# horus_psu.net
KiCad netlist of a schematic drawn in Altium Designer
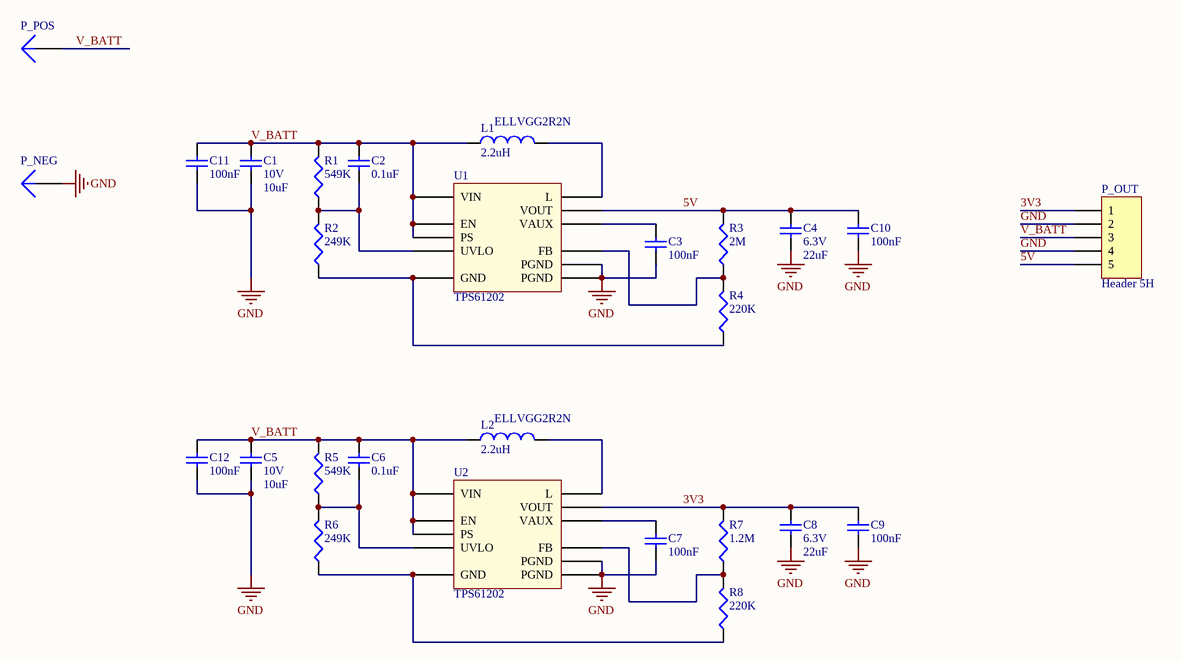
[diagram p0: horus_psu.SchDoc]

(export (version "E")
  (design (tool "Eeschema 10.0.6"))
  (components
    (comp (ref "C1")
      (value "10V")
      (footprint "C1206")
      (description "Capacitor (Semiconductor SIM Model)")
      (fields (field (name "ALTIUM_VALUE") "10uF") (field (name "PUBLISHER") "Altium Limited"))
      (libsource (lib "Miscellaneous Devices") (part "Cap Semi"))
    )
    (comp (ref "C2")
      (value "0.1uF")
      (footprint "1608[0603]")
      (description "Capacitor (Semiconductor SIM Model)")
      (fields (field (name "Comment") "Cap Semi") (field (name "PUBLISHER") "Altium Limited"))
      (libsource (lib "Miscellaneous Devices") (part "Cap Semi"))
    )
    (comp (ref "C3")
      (value "100nF")
      (footprint "1608[0603]")
      (description "Capacitor (Semiconductor SIM Model)")
      (fields (field (name "Comment") "Cap Semi") (field (name "PUBLISHER") "Altium Limited"))
      (libsource (lib "Miscellaneous Devices") (part "Cap Semi"))
    )
    (comp (ref "C4")
      (value "6.3V")
      (footprint "6-0805_N")
      (description "Capacitor (Semiconductor SIM Model)")
      (fields (field (name "ALTIUM_VALUE") "22uF") (field (name "PUBLISHER") "Altium Limited"))
      (libsource (lib "Miscellaneous Devices") (part "Cap Semi"))
    )
    (comp (ref "C5")
      (value "10V")
      (footprint "C1206")
      (description "Capacitor (Semiconductor SIM Model)")
      (fields (field (name "ALTIUM_VALUE") "10uF") (field (name "PUBLISHER") "Altium Limited"))
      (libsource (lib "Miscellaneous Devices") (part "Cap Semi"))
    )
    (comp (ref "C6")
      (value "0.1uF")
      (footprint "1608[0603]")
      (description "Capacitor (Semiconductor SIM Model)")
      (fields (field (name "Comment") "Cap Semi") (field (name "PUBLISHER") "Altium Limited"))
      (libsource (lib "Miscellaneous Devices") (part "Cap Semi"))
    )
    (comp (ref "C7")
      (value "100nF")
      (footprint "1608[0603]")
      (description "Capacitor (Semiconductor SIM Model)")
      (fields (field (name "Comment") "Cap Semi") (field (name "PUBLISHER") "Altium Limited"))
      (libsource (lib "Miscellaneous Devices") (part "Cap Semi"))
    )
    (comp (ref "C8")
      (value "6.3V")
      (footprint "6-0805_N")
      (description "Capacitor (Semiconductor SIM Model)")
      (fields (field (name "ALTIUM_VALUE") "22uF") (field (name "PUBLISHER") "Altium Limited"))
      (libsource (lib "Miscellaneous Devices") (part "Cap Semi"))
    )
    (comp (ref "C9")
      (value "100nF")
      (footprint "1608[0603]")
      (description "Capacitor (Semiconductor SIM Model)")
      (fields (field (name "Comment") "Cap Semi") (field (name "PUBLISHER") "Altium Limited"))
      (libsource (lib "Miscellaneous Devices") (part "Cap Semi"))
    )
    (comp (ref "C10")
      (value "100nF")
      (footprint "1608[0603]")
      (description "Capacitor (Semiconductor SIM Model)")
      (fields (field (name "Comment") "Cap Semi") (field (name "PUBLISHER") "Altium Limited"))
      (libsource (lib "Miscellaneous Devices") (part "Cap Semi"))
    )
    (comp (ref "C11")
      (value "100nF")
      (footprint "1608[0603]")
      (description "Capacitor (Semiconductor SIM Model)")
      (fields (field (name "Comment") "Cap Semi") (field (name "PUBLISHER") "Altium Limited"))
      (libsource (lib "Miscellaneous Devices") (part "Cap Semi"))
    )
    (comp (ref "C12")
      (value "100nF")
      (footprint "1608[0603]")
      (description "Capacitor (Semiconductor SIM Model)")
      (fields (field (name "Comment") "Cap Semi") (field (name "PUBLISHER") "Altium Limited"))
      (libsource (lib "Miscellaneous Devices") (part "Cap Semi"))
    )
    (comp (ref "L1")
      (value "ELLVGG2R2N")
      (footprint "ELLVGG")
      (description "Inductor")
      (fields (field (name "ALTIUM_VALUE") "2.2uH") (field (name "PUBLISHER") "Altium Limited"))
      (libsource (lib "Miscellaneous Devices") (part "Inductor"))
    )
    (comp (ref "L2")
      (value "ELLVGG2R2N")
      (footprint "ELLVGG")
      (description "Inductor")
      (fields (field (name "ALTIUM_VALUE") "2.2uH") (field (name "PUBLISHER") "Altium Limited"))
      (libsource (lib "Miscellaneous Devices") (part "Inductor"))
    )
    (comp (ref "P_NEG")
      (value "Plug")
      (footprint "PIN1")
      (fields (field (name "PUBLISHER") "Altium Limited"))
      (libsource (lib "Miscellaneous Connectors") (part "Plug"))
    )
    (comp (ref "P_OUT")
      (value "Header 5H")
      (footprint "HDR1X5H")
      (description "Header, 5-Pin, Right Angle")
      (fields (field (name "PUBLISHER") "Altium Limited"))
      (libsource (lib "Miscellaneous Connectors") (part "Header 5H"))
    )
    (comp (ref "P_POS")
      (value "Plug")
      (footprint "PIN1")
      (fields (field (name "PUBLISHER") "Altium Limited"))
      (libsource (lib "Miscellaneous Connectors") (part "Plug"))
    )
    (comp (ref "R1")
      (value "549K")
      (footprint "J1-0603")
      (description "Resistor")
      (fields (field (name "Comment") "Res3") (field (name "PUBLISHER") "Altium Limited"))
      (libsource (lib "Miscellaneous Devices") (part "Res3"))
    )
    (comp (ref "R2")
      (value "249K")
      (footprint "J1-0603")
      (description "Resistor")
      (fields (field (name "Comment") "Res3") (field (name "PUBLISHER") "Altium Limited"))
      (libsource (lib "Miscellaneous Devices") (part "Res3"))
    )
    (comp (ref "R3")
      (value "2M")
      (description "Resistor")
      (fields (field (name "Comment") "Res3") (field (name "PUBLISHER") "Altium Limited"))
      (libsource (lib "Miscellaneous Devices") (part "Res3"))
    )
    (comp (ref "R4")
      (value "220K")
      (description "Resistor")
      (fields (field (name "Comment") "Res3") (field (name "PUBLISHER") "Altium Limited"))
      (libsource (lib "Miscellaneous Devices") (part "Res3"))
    )
    (comp (ref "R5")
      (value "549K")
      (footprint "J1-0603")
      (description "Resistor")
      (fields (field (name "Comment") "Res3") (field (name "PUBLISHER") "Altium Limited"))
      (libsource (lib "Miscellaneous Devices") (part "Res3"))
    )
    (comp (ref "R6")
      (value "249K")
      (footprint "J1-0603")
      (description "Resistor")
      (fields (field (name "Comment") "Res3") (field (name "PUBLISHER") "Altium Limited"))
      (libsource (lib "Miscellaneous Devices") (part "Res3"))
    )
    (comp (ref "R7")
      (value "1.2M")
      (description "Resistor")
      (fields (field (name "Comment") "Res3") (field (name "PUBLISHER") "Altium Limited"))
      (libsource (lib "Miscellaneous Devices") (part "Res3"))
    )
    (comp (ref "R8")
      (value "220K")
      (description "Resistor")
      (fields (field (name "Comment") "Res3") (field (name "PUBLISHER") "Altium Limited"))
      (libsource (lib "Miscellaneous Devices") (part "Res3"))
    )
    (comp (ref "U1")
      (value "TPS61202")
      (footprint "TPS61200")
      (libsource (lib "horus_psu") (part "TPS61200"))
    )
    (comp (ref "U2")
      (value "TPS61202")
      (footprint "TPS61200")
      (libsource (lib "horus_psu") (part "TPS61200"))
    )
  )
  (nets
    (net (code "1") (name "/3V3") (class "Default")
      (node (ref "C8") (pin "2") (pinfunction "2_2") (pintype "passive"))
      (node (ref "C9") (pin "2") (pinfunction "2_2") (pintype "passive"))
      (node (ref "P_OUT") (pin "1") (pinfunction "1_1") (pintype "passive"))
      (node (ref "R7") (pin "2") (pinfunction "2_2") (pintype "passive"))
      (node (ref "U2") (pin "2") (pinfunction "VOUT_2") (pintype "passive"))
    )
    (net (code "2") (name "/5V") (class "Default")
      (node (ref "C10") (pin "2") (pinfunction "2_2") (pintype "passive"))
      (node (ref "C4") (pin "2") (pinfunction "2_2") (pintype "passive"))
      (node (ref "P_OUT") (pin "5") (pinfunction "5_5") (pintype "passive"))
      (node (ref "R3") (pin "2") (pinfunction "2_2") (pintype "passive"))
      (node (ref "U1") (pin "2") (pinfunction "VOUT_2") (pintype "passive"))
    )
    (net (code "3") (name "/V_BATT") (class "Default")
      (node (ref "C1") (pin "2") (pinfunction "2_2") (pintype "passive"))
      (node (ref "C11") (pin "2") (pinfunction "2_2") (pintype "passive"))
      (node (ref "C12") (pin "2") (pinfunction "2_2") (pintype "passive"))
      (node (ref "C2") (pin "2") (pinfunction "2_2") (pintype "passive"))
      (node (ref "C5") (pin "2") (pinfunction "2_2") (pintype "passive"))
      (node (ref "C6") (pin "2") (pinfunction "2_2") (pintype "passive"))
      (node (ref "L1") (pin "1") (pinfunction "1_1") (pintype "passive"))
      (node (ref "L2") (pin "1") (pinfunction "1_1") (pintype "passive"))
      (node (ref "P_OUT") (pin "3") (pinfunction "3_3") (pintype "passive"))
      (node (ref "P_POS") (pin "1") (pinfunction "1_1") (pintype "passive"))
      (node (ref "R1") (pin "2") (pinfunction "2_2") (pintype "passive"))
      (node (ref "R5") (pin "2") (pinfunction "2_2") (pintype "passive"))
      (node (ref "U1") (pin "5") (pinfunction "VIN_5") (pintype "passive"))
      (node (ref "U1") (pin "6") (pinfunction "EN_6") (pintype "passive"))
      (node (ref "U1") (pin "8") (pinfunction "PS_8") (pintype "passive"))
      (node (ref "U2") (pin "5") (pinfunction "VIN_5") (pintype "passive"))
      (node (ref "U2") (pin "6") (pinfunction "EN_6") (pintype "passive"))
      (node (ref "U2") (pin "8") (pinfunction "PS_8") (pintype "passive"))
    )
    (net (code "4") (name "GND") (class "Default")
      (node (ref "C1") (pin "1") (pinfunction "1_1") (pintype "passive"))
      (node (ref "C10") (pin "1") (pinfunction "1_1") (pintype "passive"))
      (node (ref "C11") (pin "1") (pinfunction "1_1") (pintype "passive"))
      (node (ref "C12") (pin "1") (pinfunction "1_1") (pintype "passive"))
      (node (ref "C3") (pin "1") (pinfunction "1_1") (pintype "passive"))
      (node (ref "C4") (pin "1") (pinfunction "1_1") (pintype "passive"))
      (node (ref "C5") (pin "1") (pinfunction "1_1") (pintype "passive"))
      (node (ref "C7") (pin "1") (pinfunction "1_1") (pintype "passive"))
      (node (ref "C8") (pin "1") (pinfunction "1_1") (pintype "passive"))
      (node (ref "C9") (pin "1") (pinfunction "1_1") (pintype "passive"))
      (node (ref "P_NEG") (pin "1") (pinfunction "1_1") (pintype "passive"))
      (node (ref "P_OUT") (pin "2") (pinfunction "2_2") (pintype "passive"))
      (node (ref "P_OUT") (pin "4") (pinfunction "4_4") (pintype "passive"))
      (node (ref "U1") (pin "0") (pinfunction "PGND_0") (pintype "passive"))
      (node (ref "U1") (pin "4") (pinfunction "PGND_4") (pintype "passive"))
      (node (ref "U2") (pin "0") (pinfunction "PGND_0") (pintype "passive"))
      (node (ref "U2") (pin "4") (pinfunction "PGND_4") (pintype "passive"))
    )
    (net (code "5") (name "Net-(U1-FB)") (class "Default")
      (node (ref "R3") (pin "1") (pinfunction "1_1") (pintype "passive"))
      (node (ref "R4") (pin "2") (pinfunction "2_2") (pintype "passive"))
      (node (ref "U1") (pin "10") (pinfunction "FB_10") (pintype "passive"))
    )
    (net (code "6") (name "Net-(U1-GND)") (class "Default")
      (node (ref "R2") (pin "1") (pinfunction "1_1") (pintype "passive"))
      (node (ref "R4") (pin "1") (pinfunction "1_1") (pintype "passive"))
      (node (ref "U1") (pin "9") (pinfunction "GND_9") (pintype "passive"))
    )
    (net (code "7") (name "Net-(U1-L)") (class "Default")
      (node (ref "L1") (pin "2") (pinfunction "2_2") (pintype "passive"))
      (node (ref "U1") (pin "3") (pinfunction "L_3") (pintype "passive"))
    )
    (net (code "8") (name "Net-(U1-UVLO)") (class "Default")
      (node (ref "C2") (pin "1") (pinfunction "1_1") (pintype "passive"))
      (node (ref "R1") (pin "1") (pinfunction "1_1") (pintype "passive"))
      (node (ref "R2") (pin "2") (pinfunction "2_2") (pintype "passive"))
      (node (ref "U1") (pin "7") (pinfunction "UVLO_7") (pintype "passive"))
    )
    (net (code "9") (name "Net-(U1-VAUX)") (class "Default")
      (node (ref "C3") (pin "2") (pinfunction "2_2") (pintype "passive"))
      (node (ref "U1") (pin "1") (pinfunction "VAUX_1") (pintype "passive"))
    )
    (net (code "10") (name "Net-(U2-FB)") (class "Default")
      (node (ref "R7") (pin "1") (pinfunction "1_1") (pintype "passive"))
      (node (ref "R8") (pin "2") (pinfunction "2_2") (pintype "passive"))
      (node (ref "U2") (pin "10") (pinfunction "FB_10") (pintype "passive"))
    )
    (net (code "11") (name "Net-(U2-GND)") (class "Default")
      (node (ref "R6") (pin "1") (pinfunction "1_1") (pintype "passive"))
      (node (ref "R8") (pin "1") (pinfunction "1_1") (pintype "passive"))
      (node (ref "U2") (pin "9") (pinfunction "GND_9") (pintype "passive"))
    )
    (net (code "12") (name "Net-(U2-L)") (class "Default")
      (node (ref "L2") (pin "2") (pinfunction "2_2") (pintype "passive"))
      (node (ref "U2") (pin "3") (pinfunction "L_3") (pintype "passive"))
    )
    (net (code "13") (name "Net-(U2-UVLO)") (class "Default")
      (node (ref "C6") (pin "1") (pinfunction "1_1") (pintype "passive"))
      (node (ref "R5") (pin "1") (pinfunction "1_1") (pintype "passive"))
      (node (ref "R6") (pin "2") (pinfunction "2_2") (pintype "passive"))
      (node (ref "U2") (pin "7") (pinfunction "UVLO_7") (pintype "passive"))
    )
    (net (code "14") (name "Net-(U2-VAUX)") (class "Default")
      (node (ref "C7") (pin "2") (pinfunction "2_2") (pintype "passive"))
      (node (ref "U2") (pin "1") (pinfunction "VAUX_1") (pintype "passive"))
    )
  )
)
